# KAI.net
KiCad netlist of a schematic drawn in Altium Designer
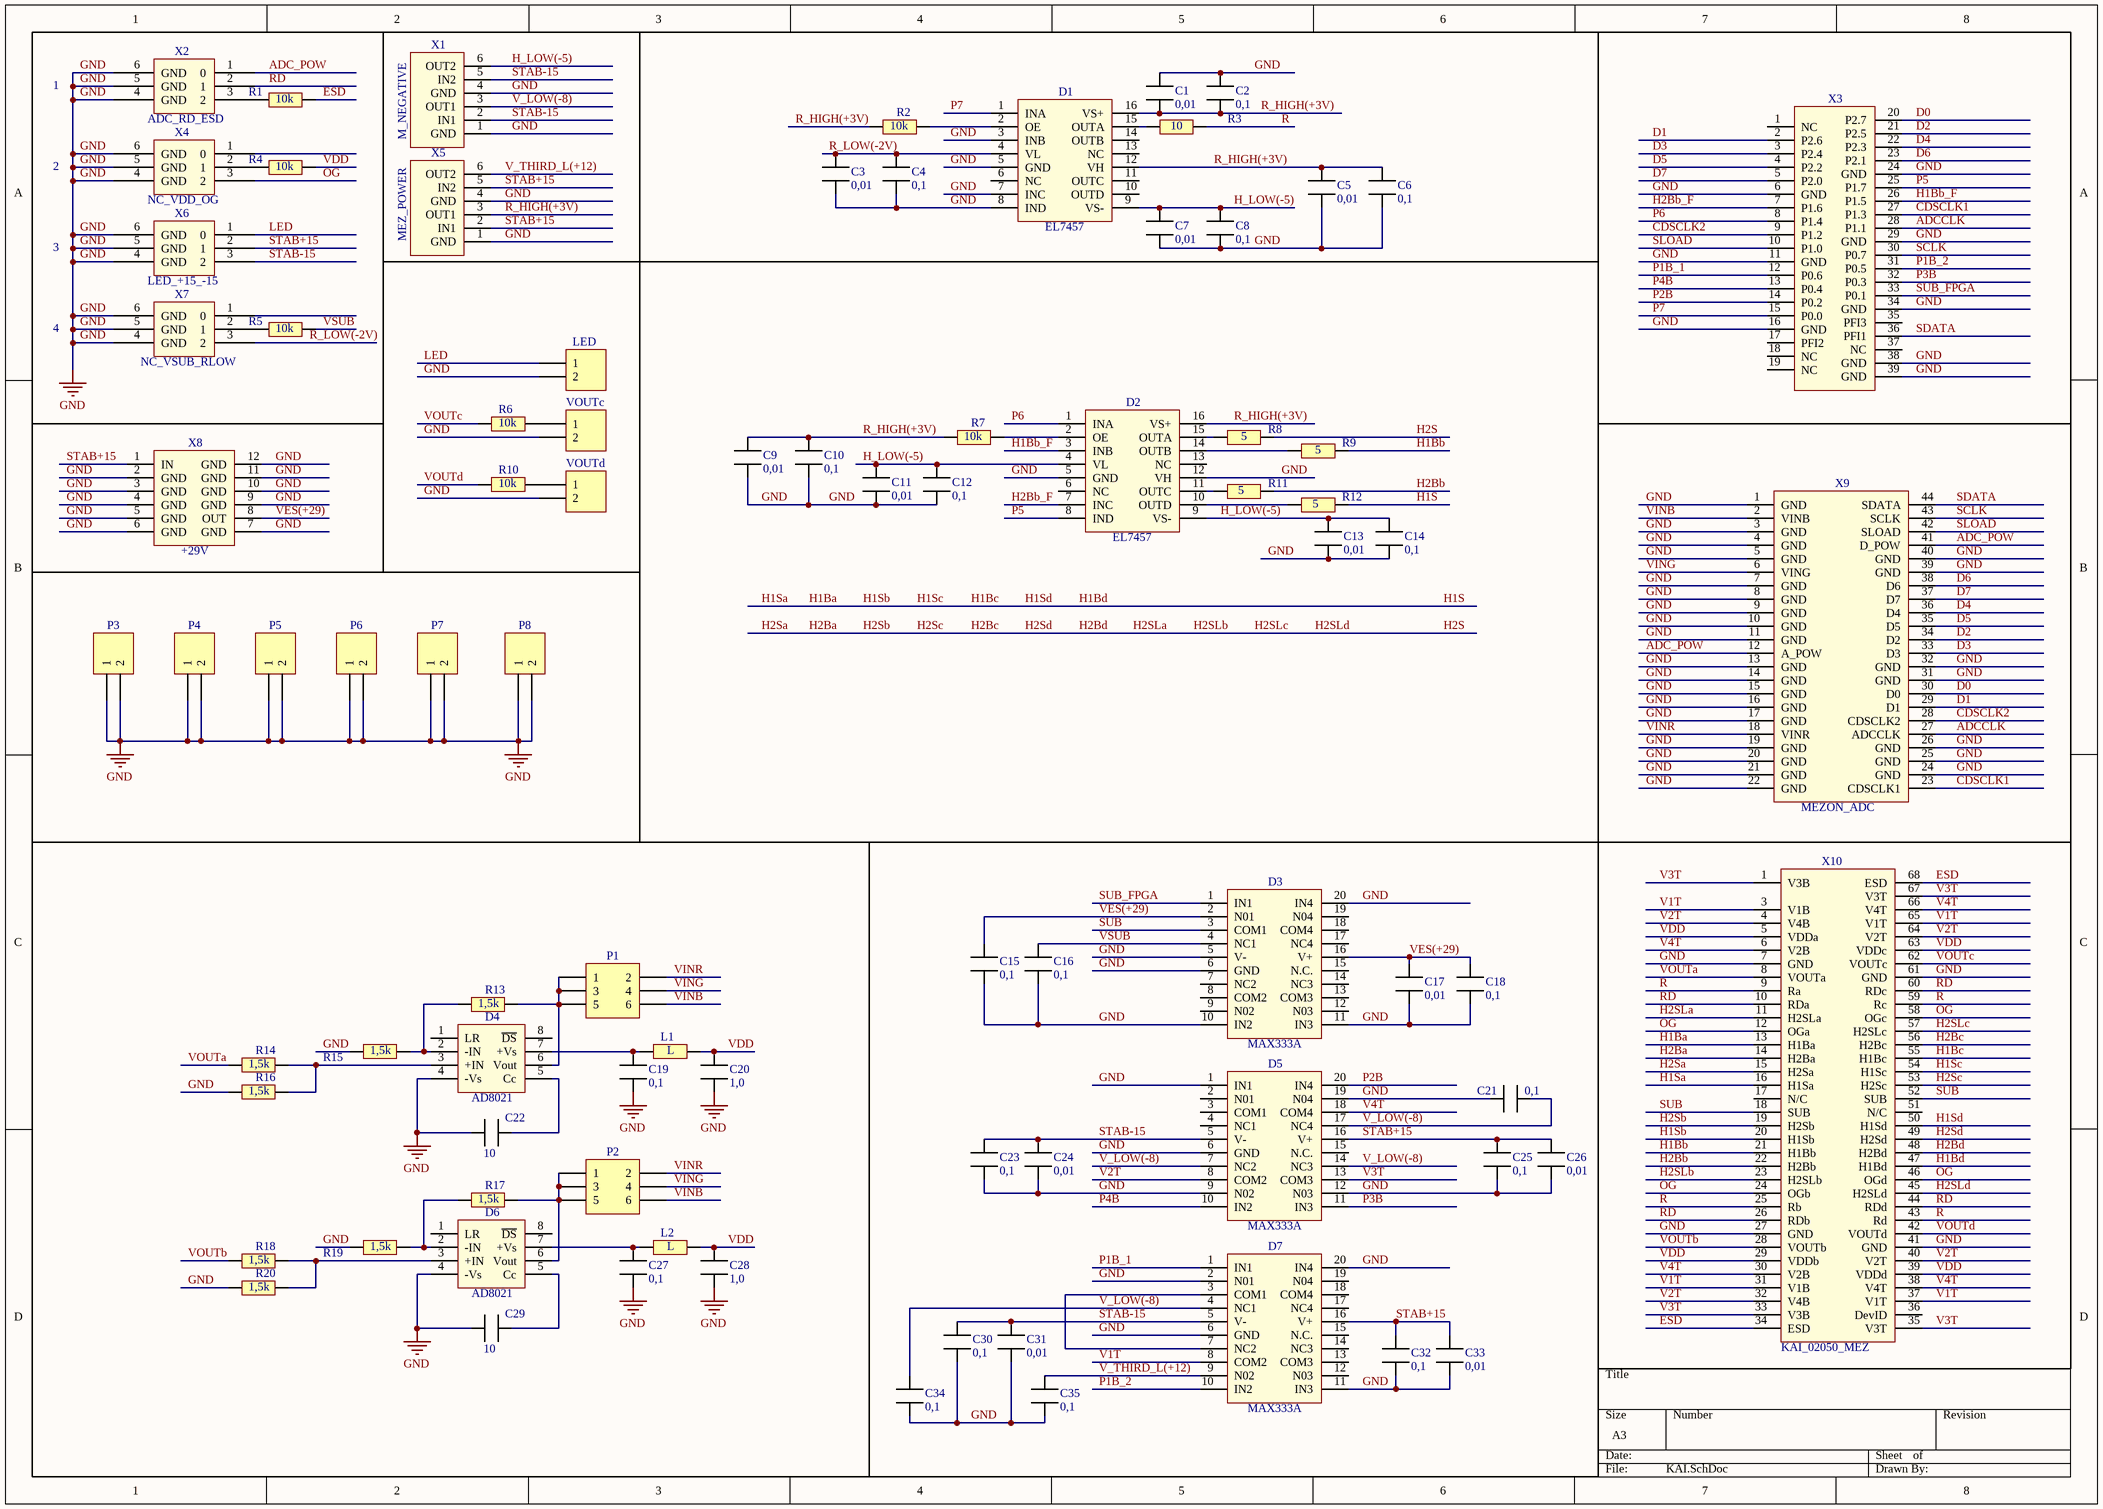
[diagram p0: KAI.SchDoc]

(export (version "E")
  (design (tool "Eeschema 10.0.6"))
  (components
    (comp (ref "C1") (value "0,01") (footprint "CAP_SMALL") (libsource (lib "Schlib") (part "CAP_SMALL")))
    (comp (ref "C2") (value "0,1") (footprint "CAP_SMALL") (libsource (lib "Schlib") (part "CAP_SMALL")))
    (comp (ref "C3") (value "0,01") (footprint "CAP_SMALL") (libsource (lib "Schlib") (part "CAP_SMALL")))
    (comp (ref "C4") (value "0,1") (footprint "CAP_SMALL") (libsource (lib "Schlib") (part "CAP_SMALL")))
    (comp (ref "C5") (value "0,01") (footprint "CAP_SMALL") (libsource (lib "Schlib") (part "CAP_SMALL")))
    (comp (ref "C6") (value "0,1") (footprint "CAP_SMALL") (libsource (lib "Schlib") (part "CAP_SMALL")))
    (comp (ref "C7") (value "0,01") (footprint "CAP_SMALL") (libsource (lib "Schlib") (part "CAP_SMALL")))
    (comp (ref "C8") (value "0,1") (footprint "CAP_SMALL") (libsource (lib "Schlib") (part "CAP_SMALL")))
    (comp (ref "C9") (value "0,01") (footprint "CAP_SMALL") (libsource (lib "Schlib") (part "CAP_SMALL")))
    (comp (ref "C10") (value "0,1") (footprint "CAP_SMALL") (libsource (lib "Schlib") (part "CAP_SMALL")))
    (comp (ref "C11") (value "0,01") (footprint "CAP_SMALL") (libsource (lib "Schlib") (part "CAP_SMALL")))
    (comp (ref "C12") (value "0,1") (footprint "CAP_SMALL") (libsource (lib "Schlib") (part "CAP_SMALL")))
    (comp (ref "C13") (value "0,01") (footprint "CAP_SMALL") (libsource (lib "Schlib") (part "CAP_SMALL")))
    (comp (ref "C14") (value "0,1") (footprint "CAP_SMALL") (libsource (lib "Schlib") (part "CAP_SMALL")))
    (comp (ref "C15") (value "0,1") (footprint "CAP_SMALL") (libsource (lib "Schlib") (part "CAP_SMALL")))
    (comp (ref "C16") (value "0,1") (footprint "CAP_SMALL") (libsource (lib "Schlib") (part "CAP_SMALL")))
    (comp (ref "C17") (value "0,01") (footprint "CAP_SMALL") (libsource (lib "Schlib") (part "CAP_SMALL")))
    (comp (ref "C18") (value "0,1") (footprint "CAP_SMALL") (libsource (lib "Schlib") (part "CAP_SMALL")))
    (comp (ref "C19") (value "0,1") (footprint "CAP_SMALL") (libsource (lib "Schlib") (part "CAP_SMALL")))
    (comp (ref "C20") (value "1,0") (footprint "CAP_SMALL") (libsource (lib "Schlib") (part "CAP_SMALL")))
    (comp (ref "C21") (value "0,1") (footprint "CAP_SMALL") (libsource (lib "Schlib") (part "CAP_SMALL")))
    (comp (ref "C22") (value "10") (footprint "CAP_SMALL") (libsource (lib "Schlib") (part "CAP_SMALL")))
    (comp (ref "C23") (value "0,1") (footprint "CAP_SMALL") (libsource (lib "Schlib") (part "CAP_SMALL")))
    (comp (ref "C24") (value "0,01") (footprint "CAP_SMALL") (libsource (lib "Schlib") (part "CAP_SMALL")))
    (comp (ref "C25") (value "0,1") (footprint "CAP_SMALL") (libsource (lib "Schlib") (part "CAP_SMALL")))
    (comp (ref "C26") (value "0,01") (footprint "CAP_SMALL") (libsource (lib "Schlib") (part "CAP_SMALL")))
    (comp (ref "C27") (value "0,1") (footprint "CAP_SMALL") (libsource (lib "Schlib") (part "CAP_SMALL")))
    (comp (ref "C28") (value "1,0") (footprint "CAP_SMALL") (libsource (lib "Schlib") (part "CAP_SMALL")))
    (comp (ref "C29") (value "10") (footprint "CAP_SMALL") (libsource (lib "Schlib") (part "CAP_SMALL")))
    (comp (ref "C30") (value "0,1") (footprint "CAP_SMALL") (libsource (lib "Schlib") (part "CAP_SMALL")))
    (comp (ref "C31") (value "0,01") (footprint "CAP_SMALL") (libsource (lib "Schlib") (part "CAP_SMALL")))
    (comp (ref "C32") (value "0,1") (footprint "CAP_SMALL") (libsource (lib "Schlib") (part "CAP_SMALL")))
    (comp (ref "C33") (value "0,01") (footprint "CAP_SMALL") (libsource (lib "Schlib") (part "CAP_SMALL")))
    (comp (ref "C34") (value "0,1") (footprint "CAP_SMALL") (libsource (lib "Schlib") (part "CAP_SMALL")))
    (comp (ref "C35") (value "0,1") (footprint "CAP_SMALL") (libsource (lib "Schlib") (part "CAP_SMALL")))
    (comp (ref "D1") (value "EL7457") (footprint "EL7457") (libsource (lib "Schlib") (part "EL7457")))
    (comp (ref "D2") (value "EL7457") (footprint "EL7457") (libsource (lib "Schlib") (part "EL7457")))
    (comp (ref "D3") (value "MAX333A") (footprint "MAX333A") (libsource (lib "Schlib") (part "MAX333A")))
    (comp (ref "D4") (value "AD8021") (footprint "AD8021") (libsource (lib "Schlib") (part "AD8021")))
    (comp (ref "D5") (value "MAX333A") (footprint "MAX333A") (libsource (lib "Schlib") (part "MAX333A")))
    (comp (ref "D6") (value "AD8021") (footprint "AD8021") (libsource (lib "Schlib") (part "AD8021")))
    (comp (ref "D7") (value "MAX333A") (footprint "MAX333A") (libsource (lib "Schlib") (part "MAX333A")))
    (comp (ref "L1") (value "L") (footprint "RES") (libsource (lib "Schlib") (part "RES")))
    (comp (ref "L2") (value "L") (footprint "RES") (libsource (lib "Schlib") (part "RES")))
    (comp (ref "LED")
      (value "Header 2")
      (footprint "HDR1X2")
      (description "Header, 2-Pin")
      (fields (field (name "PUBLISHER") "Altium Limited"))
      (libsource (lib "") (part "Header 2_1"))
    )
    (comp (ref "P1")
      (value "Header 3X2")
      (footprint "HDR2X3")
      (description "Header, 3-Pin, Dual row")
      (fields (field (name "PUBLISHER") "Altium Limited"))
      (libsource (lib "Miscellaneous Connectors") (part "Header 3X2"))
    )
    (comp (ref "P2")
      (value "Header 3X2")
      (footprint "HDR2X3")
      (description "Header, 3-Pin, Dual row")
      (fields (field (name "PUBLISHER") "Altium Limited"))
      (libsource (lib "Miscellaneous Connectors") (part "Header 3X2"))
    )
    (comp (ref "P3")
      (value "~")
      (footprint "HDR1X2")
      (description "Header, 2-Pin")
      (fields (field (name "PUBLISHER") "Altium Limited"))
      (libsource (lib "Miscellaneous Connectors") (part "Header 2"))
    )
    (comp (ref "P4")
      (value "~")
      (footprint "HDR1X2")
      (description "Header, 2-Pin")
      (fields (field (name "PUBLISHER") "Altium Limited"))
      (libsource (lib "Miscellaneous Connectors") (part "Header 2"))
    )
    (comp (ref "P5")
      (value "~")
      (footprint "HDR1X2")
      (description "Header, 2-Pin")
      (fields (field (name "PUBLISHER") "Altium Limited"))
      (libsource (lib "Miscellaneous Connectors") (part "Header 2"))
    )
    (comp (ref "P6")
      (value "~")
      (footprint "HDR1X2")
      (description "Header, 2-Pin")
      (fields (field (name "PUBLISHER") "Altium Limited"))
      (libsource (lib "Miscellaneous Connectors") (part "Header 2"))
    )
    (comp (ref "P7")
      (value "~")
      (footprint "HDR1X2")
      (description "Header, 2-Pin")
      (fields (field (name "PUBLISHER") "Altium Limited"))
      (libsource (lib "Miscellaneous Connectors") (part "Header 2"))
    )
    (comp (ref "P8")
      (value "~")
      (footprint "HDR1X2")
      (description "Header, 2-Pin")
      (fields (field (name "PUBLISHER") "Altium Limited"))
      (libsource (lib "Miscellaneous Connectors") (part "Header 2"))
    )
    (comp (ref "R1") (value "10k") (footprint "RES") (libsource (lib "Schlib") (part "RES")))
    (comp (ref "R2") (value "10k") (footprint "RES") (libsource (lib "Schlib") (part "RES")))
    (comp (ref "R3") (value "10") (footprint "RES") (libsource (lib "Schlib") (part "RES")))
    (comp (ref "R4") (value "10k") (footprint "RES") (libsource (lib "Schlib") (part "RES")))
    (comp (ref "R5") (value "10k") (footprint "RES") (libsource (lib "Schlib") (part "RES")))
    (comp (ref "R6") (value "10k") (footprint "RES") (libsource (lib "Schlib") (part "RES")))
    (comp (ref "R7") (value "10k") (footprint "RES") (libsource (lib "Schlib") (part "RES")))
    (comp (ref "R8") (value "5") (footprint "RES") (libsource (lib "Schlib") (part "RES")))
    (comp (ref "R9") (value "5") (footprint "RES") (libsource (lib "Schlib") (part "RES")))
    (comp (ref "R10") (value "10k") (footprint "RES") (libsource (lib "Schlib") (part "RES")))
    (comp (ref "R11") (value "5") (footprint "RES") (libsource (lib "Schlib") (part "RES")))
    (comp (ref "R12") (value "5") (footprint "RES") (libsource (lib "Schlib") (part "RES")))
    (comp (ref "R13") (value "1,5k") (footprint "RES") (libsource (lib "") (part "RES_1")))
    (comp (ref "R14") (value "1,5k") (footprint "RES") (libsource (lib "Schlib") (part "RES")))
    (comp (ref "R15") (value "1,5k") (footprint "RES") (libsource (lib "") (part "RES_1")))
    (comp (ref "R16") (value "1,5k") (footprint "RES") (libsource (lib "Schlib") (part "RES")))
    (comp (ref "R17") (value "1,5k") (footprint "RES") (libsource (lib "") (part "RES_1")))
    (comp (ref "R18") (value "1,5k") (footprint "RES") (libsource (lib "Schlib") (part "RES")))
    (comp (ref "R19") (value "1,5k") (footprint "RES") (libsource (lib "") (part "RES_1")))
    (comp (ref "R20") (value "1,5k") (footprint "RES") (libsource (lib "Schlib") (part "RES")))
    (comp (ref "VOUTc")
      (value "Header 2")
      (footprint "HDR1X2")
      (description "Header, 2-Pin")
      (fields (field (name "PUBLISHER") "Altium Limited"))
      (libsource (lib "") (part "Header 2_1"))
    )
    (comp (ref "VOUTd")
      (value "Header 2")
      (footprint "HDR1X2")
      (description "Header, 2-Pin")
      (fields (field (name "PUBLISHER") "Altium Limited"))
      (libsource (lib "") (part "Header 2_1"))
    )
    (comp (ref "X1")
      (value "M_NEGATIVE")
      (footprint "MEZON_POWER_NEGATIVE")
      (libsource (lib "Schlib") (part "MEZON_POWER_NEGATIVE"))
    )
    (comp (ref "X2") (value "ADC_RD_ESD") (footprint "POWER") (libsource (lib "Schlib") (part "POWER")))
    (comp (ref "X3")
      (value "CHEAP_CON_37_FEMALE")
      (footprint "CHEAP_CONN_FEMALE")
      (libsource (lib "Schlib") (part "CHEAP_CON_37_FEMALE"))
    )
    (comp (ref "X4") (value "NC_VDD_OG") (footprint "POWER") (libsource (lib "Schlib") (part "POWER")))
    (comp (ref "X5")
      (value "MEZ_POWER")
      (footprint "MEZON_POWER_NEW")
      (libsource (lib "Schlib") (part "MEZON_POWER_NEW"))
    )
    (comp (ref "X6") (value "LED_+15_-15") (footprint "POWER") (libsource (lib "Schlib") (part "POWER")))
    (comp (ref "X7") (value "NC_VSUB_RLOW") (footprint "POWER") (libsource (lib "Schlib") (part "POWER")))
    (comp (ref "X8")
      (value "+29V")
      (footprint "MEZON_STEP-UP")
      (libsource (lib "Schlib") (part "MEZON_STEP-UP"))
    )
    (comp (ref "X9")
      (value "MEZON_ADC")
      (footprint "MEZON_ADC")
      (libsource (lib "Schlib") (part "MEZON_ADC"))
    )
    (comp (ref "X10")
      (value "KAI_02050_MEZ")
      (footprint "KAI_02050_MEZONIN")
      (libsource (lib "Schlib") (part "KAI_02050_MEZON"))
    )
  )
  (nets
    (net (code "1") (name "/ADCCLK") (class "Default")
      (node (ref "X3") (pin "28") (pinfunction "P1.1_28") (pintype "passive"))
      (node (ref "X9") (pin "27") (pinfunction "ADCCLK_27") (pintype "passive"))
    )
    (net (code "2") (name "/ADC_POW") (class "Default")
      (node (ref "X2") (pin "1") (pinfunction "0_1") (pintype "passive"))
      (node (ref "X9") (pin "12") (pinfunction "A_POW_12") (pintype "passive"))
      (node (ref "X9") (pin "41") (pinfunction "D_POW_41") (pintype "passive"))
    )
    (net (code "3") (name "/CDSCLK1") (class "Default")
      (node (ref "X3") (pin "27") (pinfunction "P1.3_27") (pintype "passive"))
      (node (ref "X9") (pin "23") (pinfunction "CDSCLK1_23") (pintype "passive"))
    )
    (net (code "4") (name "/CDSCLK2") (class "Default")
      (node (ref "X3") (pin "9") (pinfunction "P1.2_9") (pintype "passive"))
      (node (ref "X9") (pin "28") (pinfunction "CDSCLK2_28") (pintype "passive"))
    )
    (net (code "5") (name "/D0") (class "Default")
      (node (ref "X3") (pin "20") (pinfunction "P2.7_20") (pintype "passive"))
      (node (ref "X9") (pin "30") (pinfunction "D0_30") (pintype "passive"))
    )
    (net (code "6") (name "/D1") (class "Default")
      (node (ref "X3") (pin "2") (pinfunction "P2.6_2") (pintype "passive"))
      (node (ref "X9") (pin "29") (pinfunction "D1_29") (pintype "passive"))
    )
    (net (code "7") (name "/D2") (class "Default")
      (node (ref "X3") (pin "21") (pinfunction "P2.5_21") (pintype "passive"))
      (node (ref "X9") (pin "34") (pinfunction "D2_34") (pintype "passive"))
    )
    (net (code "8") (name "/D3") (class "Default")
      (node (ref "X3") (pin "3") (pinfunction "P2.4_3") (pintype "passive"))
      (node (ref "X9") (pin "33") (pinfunction "D3_33") (pintype "passive"))
    )
    (net (code "9") (name "/D4") (class "Default")
      (node (ref "X3") (pin "22") (pinfunction "P2.3_22") (pintype "passive"))
      (node (ref "X9") (pin "36") (pinfunction "D4_36") (pintype "passive"))
    )
    (net (code "10") (name "/D5") (class "Default")
      (node (ref "X3") (pin "4") (pinfunction "P2.2_4") (pintype "passive"))
      (node (ref "X9") (pin "35") (pinfunction "D5_35") (pintype "passive"))
    )
    (net (code "11") (name "/D6") (class "Default")
      (node (ref "X3") (pin "23") (pinfunction "P2.1_23") (pintype "passive"))
      (node (ref "X9") (pin "38") (pinfunction "D6_38") (pintype "passive"))
    )
    (net (code "12") (name "/D7") (class "Default")
      (node (ref "X3") (pin "5") (pinfunction "P2.0_5") (pintype "passive"))
      (node (ref "X9") (pin "37") (pinfunction "D7_37") (pintype "passive"))
    )
    (net (code "13") (name "/ESD") (class "Default")
      (node (ref "R1") (pin "2") (pinfunction "2_2") (pintype "passive"))
      (node (ref "X10") (pin "34") (pinfunction "ESD_34") (pintype "passive"))
      (node (ref "X10") (pin "68") (pinfunction "ESD_68") (pintype "passive"))
    )
    (net (code "14") (name "/H1Ba") (class "Default")
      (node (ref "R12") (pin "2") (pinfunction "2_2") (pintype "passive"))
      (node (ref "X10") (pin "13") (pinfunction "H1Ba_13") (pintype "passive"))
      (node (ref "X10") (pin "16") (pinfunction "H1Sa_16") (pintype "passive"))
      (node (ref "X10") (pin "20") (pinfunction "H1Sb_20") (pintype "passive"))
      (node (ref "X10") (pin "47") (pinfunction "H1Bd_47") (pintype "passive"))
      (node (ref "X10") (pin "50") (pinfunction "H1Sd_50") (pintype "passive"))
      (node (ref "X10") (pin "54") (pinfunction "H1Sc_54") (pintype "passive"))
      (node (ref "X10") (pin "55") (pinfunction "H1Bc_55") (pintype "passive"))
    )
    (net (code "15") (name "/H1Bb") (class "Default")
      (node (ref "R9") (pin "2") (pinfunction "2_2") (pintype "passive"))
      (node (ref "X10") (pin "21") (pinfunction "H1Bb_21") (pintype "passive"))
    )
    (net (code "16") (name "/H1Bb_F") (class "Default")
      (node (ref "D2") (pin "3") (pinfunction "INB_3") (pintype "passive"))
      (node (ref "X3") (pin "26") (pinfunction "P1.5_26") (pintype "passive"))
    )
    (net (code "17") (name "/H2Ba") (class "Default")
      (node (ref "R8") (pin "2") (pinfunction "2_2") (pintype "passive"))
      (node (ref "X10") (pin "11") (pinfunction "H2SLa_11") (pintype "passive"))
      (node (ref "X10") (pin "14") (pinfunction "H2Ba_14") (pintype "passive"))
      (node (ref "X10") (pin "15") (pinfunction "H2Sa_15") (pintype "passive"))
      (node (ref "X10") (pin "19") (pinfunction "H2Sb_19") (pintype "passive"))
      (node (ref "X10") (pin "23") (pinfunction "H2SLb_23") (pintype "passive"))
      (node (ref "X10") (pin "45") (pinfunction "H2SLd_45") (pintype "passive"))
      (node (ref "X10") (pin "48") (pinfunction "H2Bd_48") (pintype "passive"))
      (node (ref "X10") (pin "49") (pinfunction "H2Sd_49") (pintype "passive"))
      (node (ref "X10") (pin "53") (pinfunction "H2Sc_53") (pintype "passive"))
      (node (ref "X10") (pin "56") (pinfunction "H2Bc_56") (pintype "passive"))
      (node (ref "X10") (pin "57") (pinfunction "H2SLc_57") (pintype "passive"))
    )
    (net (code "18") (name "/H2Bb") (class "Default")
      (node (ref "R11") (pin "2") (pinfunction "2_2") (pintype "passive"))
      (node (ref "X10") (pin "22") (pinfunction "H2Bb_22") (pintype "passive"))
    )
    (net (code "19") (name "/H2Bb_F") (class "Default")
      (node (ref "D2") (pin "7") (pinfunction "INC_7") (pintype "passive"))
      (node (ref "X3") (pin "7") (pinfunction "P1.6_7") (pintype "passive"))
    )
    (net (code "20") (name "/H_LOW(-5)") (class "Default")
      (node (ref "C11") (pin "1") (pinfunction "1_1") (pintype "passive"))
      (node (ref "C12") (pin "1") (pinfunction "1_1") (pintype "passive"))
      (node (ref "C13") (pin "1") (pinfunction "1_1") (pintype "passive"))
      (node (ref "C14") (pin "1") (pinfunction "1_1") (pintype "passive"))
      (node (ref "C7") (pin "1") (pinfunction "1_1") (pintype "passive"))
      (node (ref "C8") (pin "1") (pinfunction "1_1") (pintype "passive"))
      (node (ref "D1") (pin "9") (pinfunction "VS-_9") (pintype "passive"))
      (node (ref "D2") (pin "4") (pinfunction "VL_4") (pintype "passive"))
      (node (ref "D2") (pin "9") (pinfunction "VS-_9") (pintype "passive"))
      (node (ref "X1") (pin "6") (pinfunction "OUT2_6") (pintype "passive"))
    )
    (net (code "21") (name "/LED") (class "Default")
      (node (ref "LED") (pin "1") (pinfunction "1_1") (pintype "passive"))
      (node (ref "X6") (pin "1") (pinfunction "0_1") (pintype "passive"))
    )
    (net (code "22") (name "/OG") (class "Default")
      (node (ref "X10") (pin "12") (pinfunction "OGa_12") (pintype "passive"))
      (node (ref "X10") (pin "24") (pinfunction "OGb_24") (pintype "passive"))
      (node (ref "X10") (pin "46") (pinfunction "OGd_46") (pintype "passive"))
      (node (ref "X10") (pin "58") (pinfunction "OGc_58") (pintype "passive"))
      (node (ref "X4") (pin "3") (pinfunction "2_3") (pintype "passive"))
    )
    (net (code "23") (name "/P1B_1") (class "Default")
      (node (ref "D7") (pin "1") (pinfunction "IN1_1") (pintype "passive"))
      (node (ref "X3") (pin "12") (pinfunction "P0.6_12") (pintype "passive"))
    )
    (net (code "24") (name "/P1B_2") (class "Default")
      (node (ref "D7") (pin "10") (pinfunction "IN2_10") (pintype "passive"))
      (node (ref "X3") (pin "31") (pinfunction "P0.5_31") (pintype "passive"))
    )
    (net (code "25") (name "/P2B") (class "Default")
      (node (ref "D5") (pin "20") (pinfunction "IN4_20") (pintype "passive"))
      (node (ref "X3") (pin "14") (pinfunction "P0.2_14") (pintype "passive"))
    )
    (net (code "26") (name "/P3B") (class "Default")
      (node (ref "D5") (pin "11") (pinfunction "IN3_11") (pintype "passive"))
      (node (ref "X3") (pin "32") (pinfunction "P0.3_32") (pintype "passive"))
    )
    (net (code "27") (name "/P4B") (class "Default")
      (node (ref "D5") (pin "10") (pinfunction "IN2_10") (pintype "passive"))
      (node (ref "X3") (pin "13") (pinfunction "P0.4_13") (pintype "passive"))
    )
    (net (code "28") (name "/P5") (class "Default")
      (node (ref "D2") (pin "8") (pinfunction "IND_8") (pintype "passive"))
      (node (ref "X3") (pin "25") (pinfunction "P1.7_25") (pintype "passive"))
    )
    (net (code "29") (name "/P6") (class "Default")
      (node (ref "D2") (pin "1") (pinfunction "INA_1") (pintype "passive"))
      (node (ref "X3") (pin "8") (pinfunction "P1.4_8") (pintype "passive"))
    )
    (net (code "30") (name "/P7") (class "Default")
      (node (ref "D1") (pin "1") (pinfunction "INA_1") (pintype "passive"))
      (node (ref "X3") (pin "15") (pinfunction "P0.0_15") (pintype "passive"))
    )
    (net (code "31") (name "/R") (class "Default")
      (node (ref "R3") (pin "2") (pinfunction "2_2") (pintype "passive"))
      (node (ref "X10") (pin "25") (pinfunction "Rb_25") (pintype "passive"))
      (node (ref "X10") (pin "43") (pinfunction "Rd_43") (pintype "passive"))
      (node (ref "X10") (pin "59") (pinfunction "Rc_59") (pintype "passive"))
      (node (ref "X10") (pin "9") (pinfunction "Ra_9") (pintype "passive"))
    )
    (net (code "32") (name "/RD") (class "Default")
      (node (ref "X10") (pin "10") (pinfunction "RDa_10") (pintype "passive"))
      (node (ref "X10") (pin "26") (pinfunction "RDb_26") (pintype "passive"))
      (node (ref "X10") (pin "44") (pinfunction "RDd_44") (pintype "passive"))
      (node (ref "X10") (pin "60") (pinfunction "RDc_60") (pintype "passive"))
      (node (ref "X2") (pin "2") (pinfunction "1_2") (pintype "passive"))
    )
    (net (code "33") (name "/R_HIGH(+3V)") (class "Default")
      (node (ref "C1") (pin "2") (pinfunction "2_2") (pintype "passive"))
      (node (ref "C10") (pin "1") (pinfunction "1_1") (pintype "passive"))
      (node (ref "C2") (pin "2") (pinfunction "2_2") (pintype "passive"))
      (node (ref "C5") (pin "1") (pinfunction "1_1") (pintype "passive"))
      (node (ref "C6") (pin "1") (pinfunction "1_1") (pintype "passive"))
      (node (ref "C9") (pin "1") (pinfunction "1_1") (pintype "passive"))
      (node (ref "D1") (pin "12") (pinfunction "VH_12") (pintype "passive"))
      (node (ref "D1") (pin "16") (pinfunction "VS+_16") (pintype "passive"))
      (node (ref "D2") (pin "16") (pinfunction "VS+_16") (pintype "passive"))
      (node (ref "R2") (pin "1") (pinfunction "1_1") (pintype "passive"))
      (node (ref "R7") (pin "1") (pinfunction "1_1") (pintype "passive"))
      (node (ref "X5") (pin "3") (pinfunction "OUT1_3") (pintype "passive"))
    )
    (net (code "34") (name "/R_LOW(-2V)") (class "Default")
      (node (ref "C3") (pin "1") (pinfunction "1_1") (pintype "passive"))
      (node (ref "C4") (pin "1") (pinfunction "1_1") (pintype "passive"))
      (node (ref "D1") (pin "4") (pinfunction "VL_4") (pintype "passive"))
      (node (ref "X7") (pin "3") (pinfunction "2_3") (pintype "passive"))
    )
    (net (code "35") (name "/SCLK") (class "Default")
      (node (ref "X3") (pin "30") (pinfunction "P0.7_30") (pintype "passive"))
      (node (ref "X9") (pin "43") (pinfunction "SCLK_43") (pintype "passive"))
    )
    (net (code "36") (name "/SDATA") (class "Default")
      (node (ref "X3") (pin "36") (pinfunction "PFI1_36") (pintype "passive"))
      (node (ref "X9") (pin "44") (pinfunction "SDATA_44") (pintype "passive"))
    )
    (net (code "37") (name "/SLOAD") (class "Default")
      (node (ref "X3") (pin "10") (pinfunction "P1.0_10") (pintype "passive"))
      (node (ref "X9") (pin "42") (pinfunction "SLOAD_42") (pintype "passive"))
    )
    (net (code "38") (name "/STAB+15") (class "Default")
      (node (ref "C25") (pin "2") (pinfunction "2_2") (pintype "passive"))
      (node (ref "C26") (pin "2") (pinfunction "2_2") (pintype "passive"))
      (node (ref "C32") (pin "2") (pinfunction "2_2") (pintype "passive"))
      (node (ref "C33") (pin "2") (pinfunction "2_2") (pintype "passive"))
      (node (ref "D5") (pin "16") (pinfunction "V+_16") (pintype "passive"))
      (node (ref "D7") (pin "16") (pinfunction "V+_16") (pintype "passive"))
      (node (ref "X5") (pin "2") (pinfunction "IN1_2") (pintype "passive"))
      (node (ref "X5") (pin "5") (pinfunction "IN2_5") (pintype "passive"))
      (node (ref "X6") (pin "2") (pinfunction "1_2") (pintype "passive"))
      (node (ref "X8") (pin "1") (pinfunction "IN_1") (pintype "passive"))
    )
    (net (code "39") (name "/STAB-15") (class "Default")
      (node (ref "C23") (pin "2") (pinfunction "2_2") (pintype "passive"))
      (node (ref "C24") (pin "2") (pinfunction "2_2") (pintype "passive"))
      (node (ref "C30") (pin "2") (pinfunction "2_2") (pintype "passive"))
      (node (ref "C31") (pin "2") (pinfunction "2_2") (pintype "passive"))
      (node (ref "D5") (pin "5") (pinfunction "V-_5") (pintype "passive"))
      (node (ref "D7") (pin "5") (pinfunction "V-_5") (pintype "passive"))
      (node (ref "X1") (pin "2") (pinfunction "IN1_2") (pintype "passive"))
      (node (ref "X1") (pin "5") (pinfunction "IN2_5") (pintype "passive"))
      (node (ref "X6") (pin "3") (pinfunction "2_3") (pintype "passive"))
    )
    (net (code "40") (name "/SUB") (class "Default")
      (node (ref "D3") (pin "3") (pinfunction "COM1_3") (pintype "passive"))
      (node (ref "X10") (pin "18") (pinfunction "SUB_18") (pintype "passive"))
      (node (ref "X10") (pin "52") (pinfunction "SUB_52") (pintype "passive"))
    )
    (net (code "41") (name "/SUB_FPGA") (class "Default")
      (node (ref "D3") (pin "1") (pinfunction "IN1_1") (pintype "passive"))
      (node (ref "X3") (pin "33") (pinfunction "P0.1_33") (pintype "passive"))
    )
    (net (code "42") (name "/V1T") (class "Default")
      (node (ref "D7") (pin "8") (pinfunction "COM2_8") (pintype "passive"))
      (node (ref "X10") (pin "3") (pinfunction "V1B_3") (pintype "passive"))
      (node (ref "X10") (pin "31") (pinfunction "V1B_31") (pintype "passive"))
      (node (ref "X10") (pin "37") (pinfunction "V1T_37") (pintype "passive"))
      (node (ref "X10") (pin "65") (pinfunction "V1T_65") (pintype "passive"))
    )
    (net (code "43") (name "/V2T") (class "Default")
      (node (ref "D5") (pin "8") (pinfunction "COM2_8") (pintype "passive"))
      (node (ref "X10") (pin "32") (pinfunction "V4B_32") (pintype "passive"))
      (node (ref "X10") (pin "4") (pinfunction "V4B_4") (pintype "passive"))
      (node (ref "X10") (pin "40") (pinfunction "V2T_40") (pintype "passive"))
      (node (ref "X10") (pin "64") (pinfunction "V2T_64") (pintype "passive"))
    )
    (net (code "44") (name "/V3T") (class "Default")
      (node (ref "D5") (pin "13") (pinfunction "COM3_13") (pintype "passive"))
      (node (ref "X10") (pin "1") (pinfunction "V3B_1") (pintype "passive"))
      (node (ref "X10") (pin "33") (pinfunction "V3B_33") (pintype "passive"))
      (node (ref "X10") (pin "35") (pinfunction "V3T_35") (pintype "passive"))
      (node (ref "X10") (pin "67") (pinfunction "V3T_67") (pintype "passive"))
    )
    (net (code "45") (name "/V4T") (class "Default")
      (node (ref "D5") (pin "18") (pinfunction "COM4_18") (pintype "passive"))
      (node (ref "X10") (pin "30") (pinfunction "V2B_30") (pintype "passive"))
      (node (ref "X10") (pin "38") (pinfunction "V4T_38") (pintype "passive"))
      (node (ref "X10") (pin "6") (pinfunction "V2B_6") (pintype "passive"))
      (node (ref "X10") (pin "66") (pinfunction "V4T_66") (pintype "passive"))
    )
    (net (code "46") (name "/VDD") (class "Default")
      (node (ref "C20") (pin "2") (pinfunction "2_2") (pintype "passive"))
      (node (ref "C28") (pin "2") (pinfunction "2_2") (pintype "passive"))
      (node (ref "L1") (pin "2") (pinfunction "2_2") (pintype "passive"))
      (node (ref "L2") (pin "2") (pinfunction "2_2") (pintype "passive"))
      (node (ref "R4") (pin "2") (pinfunction "2_2") (pintype "passive"))
      (node (ref "X10") (pin "29") (pinfunction "VDDb_29") (pintype "passive"))
      (node (ref "X10") (pin "39") (pinfunction "VDDd_39") (pintype "passive"))
      (node (ref "X10") (pin "5") (pinfunction "VDDa_5") (pintype "passive"))
      (node (ref "X10") (pin "63") (pinfunction "VDDc_63") (pintype "passive"))
    )
    (net (code "47") (name "/VES(+29)") (class "Default")
      (node (ref "C15") (pin "1") (pinfunction "1_1") (pintype "passive"))
      (node (ref "C17") (pin "2") (pinfunction "2_2") (pintype "passive"))
      (node (ref "C18") (pin "2") (pinfunction "2_2") (pintype "passive"))
      (node (ref "D3") (pin "16") (pinfunction "V+_16") (pintype "passive"))
      (node (ref "D3") (pin "2") (pinfunction "N01_2") (pintype "passive"))
      (node (ref "X8") (pin "8") (pinfunction "OUT_8") (pintype "passive"))
    )
    (net (code "48") (name "/VINB") (class "Default")
      (node (ref "P1") (pin "6") (pinfunction "6_6") (pintype "passive"))
      (node (ref "P2") (pin "6") (pinfunction "6_6") (pintype "passive"))
      (node (ref "X9") (pin "2") (pinfunction "VINB_2") (pintype "passive"))
    )
    (net (code "49") (name "/VING") (class "Default")
      (node (ref "P1") (pin "4") (pinfunction "4_4") (pintype "passive"))
      (node (ref "P2") (pin "4") (pinfunction "4_4") (pintype "passive"))
      (node (ref "X9") (pin "6") (pinfunction "VING_6") (pintype "passive"))
    )
    (net (code "50") (name "/VINR") (class "Default")
      (node (ref "P1") (pin "2") (pinfunction "2_2") (pintype "passive"))
      (node (ref "P2") (pin "2") (pinfunction "2_2") (pintype "passive"))
      (node (ref "X9") (pin "18") (pinfunction "VINR_18") (pintype "passive"))
    )
    (net (code "51") (name "/VOUTa") (class "Default")
      (node (ref "R14") (pin "1") (pinfunction "1_1") (pintype "passive"))
      (node (ref "X10") (pin "8") (pinfunction "VOUTa_8") (pintype "passive"))
    )
    (net (code "52") (name "/VOUTb") (class "Default")
      (node (ref "R18") (pin "1") (pinfunction "1_1") (pintype "passive"))
      (node (ref "X10") (pin "28") (pinfunction "VOUTb_28") (pintype "passive"))
    )
    (net (code "53") (name "/VOUTc") (class "Default")
      (node (ref "R6") (pin "1") (pinfunction "1_1") (pintype "passive"))
      (node (ref "X10") (pin "62") (pinfunction "VOUTc_62") (pintype "passive"))
    )
    (net (code "54") (name "/VOUTd") (class "Default")
      (node (ref "R10") (pin "1") (pinfunction "1_1") (pintype "passive"))
      (node (ref "X10") (pin "42") (pinfunction "VOUTd_42") (pintype "passive"))
    )
    (net (code "55") (name "/VSUB") (class "Default")
      (node (ref "C16") (pin "1") (pinfunction "1_1") (pintype "passive"))
      (node (ref "D3") (pin "4") (pinfunction "NC1_4") (pintype "passive"))
      (node (ref "R5") (pin "2") (pinfunction "2_2") (pintype "passive"))
    )
    (net (code "56") (name "/V_LOW(-8)") (class "Default")
      (node (ref "C21") (pin "1") (pinfunction "1_1") (pintype "passive"))
      (node (ref "C34") (pin "2") (pinfunction "2_2") (pintype "passive"))
      (node (ref "D5") (pin "14") (pinfunction "NC3_14") (pintype "passive"))
      (node (ref "D5") (pin "17") (pinfunction "NC4_17") (pintype "passive"))
      (node (ref "D5") (pin "7") (pinfunction "NC2_7") (pintype "passive"))
      (node (ref "D7") (pin "4") (pinfunction "NC1_4") (pintype "passive"))
      (node (ref "X1") (pin "3") (pinfunction "OUT1_3") (pintype "passive"))
    )
    (net (code "57") (name "/V_THIRD_L(+12)") (class "Default")
      (node (ref "C35") (pin "2") (pinfunction "2_2") (pintype "passive"))
      (node (ref "D7") (pin "9") (pinfunction "N02_9") (pintype "passive"))
      (node (ref "X5") (pin "6") (pinfunction "OUT2_6") (pintype "passive"))
    )
    (net (code "58") (name "GND") (class "Default")
      (node (ref "C1") (pin "1") (pinfunction "1_1") (pintype "passive"))
      (node (ref "C10") (pin "2") (pinfunction "2_2") (pintype "passive"))
      (node (ref "C11") (pin "2") (pinfunction "2_2") (pintype "passive"))
      (node (ref "C12") (pin "2") (pinfunction "2_2") (pintype "passive"))
      (node (ref "C13") (pin "2") (pinfunction "2_2") (pintype "passive"))
      (node (ref "C14") (pin "2") (pinfunction "2_2") (pintype "passive"))
      (node (ref "C15") (pin "2") (pinfunction "2_2") (pintype "passive"))
      (node (ref "C16") (pin "2") (pinfunction "2_2") (pintype "passive"))
      (node (ref "C17") (pin "1") (pinfunction "1_1") (pintype "passive"))
      (node (ref "C18") (pin "1") (pinfunction "1_1") (pintype "passive"))
      (node (ref "C19") (pin "1") (pinfunction "1_1") (pintype "passive"))
      (node (ref "C2") (pin "1") (pinfunction "1_1") (pintype "passive"))
      (node (ref "C20") (pin "1") (pinfunction "1_1") (pintype "passive"))
      (node (ref "C21") (pin "2") (pinfunction "2_2") (pintype "passive"))
      (node (ref "C22") (pin "2") (pinfunction "2_2") (pintype "passive"))
      (node (ref "C23") (pin "1") (pinfunction "1_1") (pintype "passive"))
      (node (ref "C24") (pin "1") (pinfunction "1_1") (pintype "passive"))
      (node (ref "C25") (pin "1") (pinfunction "1_1") (pintype "passive"))
      (node (ref "C26") (pin "1") (pinfunction "1_1") (pintype "passive"))
      (node (ref "C27") (pin "1") (pinfunction "1_1") (pintype "passive"))
      (node (ref "C28") (pin "1") (pinfunction "1_1") (pintype "passive"))
      (node (ref "C29") (pin "2") (pinfunction "2_2") (pintype "passive"))
      (node (ref "C3") (pin "2") (pinfunction "2_2") (pintype "passive"))
      (node (ref "C30") (pin "1") (pinfunction "1_1") (pintype "passive"))
      (node (ref "C31") (pin "1") (pinfunction "1_1") (pintype "passive"))
      (node (ref "C32") (pin "1") (pinfunction "1_1") (pintype "passive"))
      (node (ref "C33") (pin "1") (pinfunction "1_1") (pintype "passive"))
      (node (ref "C34") (pin "1") (pinfunction "1_1") (pintype "passive"))
      (node (ref "C35") (pin "1") (pinfunction "1_1") (pintype "passive"))
      (node (ref "C4") (pin "2") (pinfunction "2_2") (pintype "passive"))
      (node (ref "C5") (pin "2") (pinfunction "2_2") (pintype "passive"))
      (node (ref "C6") (pin "2") (pinfunction "2_2") (pintype "passive"))
      (node (ref "C7") (pin "2") (pinfunction "2_2") (pintype "passive"))
      (node (ref "C8") (pin "2") (pinfunction "2_2") (pintype "passive"))
      (node (ref "C9") (pin "2") (pinfunction "2_2") (pintype "passive"))
      (node (ref "D1") (pin "3") (pinfunction "INB_3") (pintype "passive"))
      (node (ref "D1") (pin "5") (pinfunction "GND_5") (pintype "passive"))
      (node (ref "D1") (pin "7") (pinfunction "INC_7") (pintype "passive"))
      (node (ref "D1") (pin "8") (pinfunction "IND_8") (pintype "passive"))
      (node (ref "D2") (pin "12") (pinfunction "VH_12") (pintype "passive"))
      (node (ref "D2") (pin "5") (pinfunction "GND_5") (pintype "passive"))
      (node (ref "D3") (pin "10") (pinfunction "IN2_10") (pintype "passive"))
      (node (ref "D3") (pin "11") (pinfunction "IN3_11") (pintype "passive"))
      (node (ref "D3") (pin "20") (pinfunction "IN4_20") (pintype "passive"))
      (node (ref "D3") (pin "5") (pinfunction "V-_5") (pintype "passive"))
      (node (ref "D3") (pin "6") (pinfunction "GND_6") (pintype "passive"))
      (node (ref "D4") (pin "4") (pinfunction "-Vs_4") (pintype "passive"))
      (node (ref "D5") (pin "1") (pinfunction "IN1_1") (pintype "passive"))
      (node (ref "D5") (pin "12") (pinfunction "N03_12") (pintype "passive"))
      (node (ref "D5") (pin "19") (pinfunction "N04_19") (pintype "passive"))
      (node (ref "D5") (pin "6") (pinfunction "GND_6") (pintype "passive"))
      (node (ref "D5") (pin "9") (pinfunction "N02_9") (pintype "passive"))
      (node (ref "D6") (pin "4") (pinfunction "-Vs_4") (pintype "passive"))
      (node (ref "D7") (pin "11") (pinfunction "IN3_11") (pintype "passive"))
      (node (ref "D7") (pin "2") (pinfunction "N01_2") (pintype "passive"))
      (node (ref "D7") (pin "20") (pinfunction "IN4_20") (pintype "passive"))
      (node (ref "D7") (pin "6") (pinfunction "GND_6") (pintype "passive"))
      (node (ref "LED") (pin "2") (pinfunction "2_2") (pintype "passive"))
      (node (ref "P3") (pin "1") (pinfunction "1_1") (pintype "passive"))
      (node (ref "P3") (pin "2") (pinfunction "2_2") (pintype "passive"))
      (node (ref "P4") (pin "1") (pinfunction "1_1") (pintype "passive"))
      (node (ref "P4") (pin "2") (pinfunction "2_2") (pintype "passive"))
      (node (ref "P5") (pin "1") (pinfunction "1_1") (pintype "passive"))
      (node (ref "P5") (pin "2") (pinfunction "2_2") (pintype "passive"))
      (node (ref "P6") (pin "1") (pinfunction "1_1") (pintype "passive"))
      (node (ref "P6") (pin "2") (pinfunction "2_2") (pintype "passive"))
      (node (ref "P7") (pin "1") (pinfunction "1_1") (pintype "passive"))
      (node (ref "P7") (pin "2") (pinfunction "2_2") (pintype "passive"))
      (node (ref "P8") (pin "1") (pinfunction "1_1") (pintype "passive"))
      (node (ref "P8") (pin "2") (pinfunction "2_2") (pintype "passive"))
      (node (ref "R15") (pin "2") (pinfunction "2_2") (pintype "passive"))
      (node (ref "R16") (pin "1") (pinfunction "1_1") (pintype "passive"))
      (node (ref "R19") (pin "2") (pinfunction "2_2") (pintype "passive"))
      (node (ref "R20") (pin "1") (pinfunction "1_1") (pintype "passive"))
      (node (ref "VOUTc") (pin "2") (pinfunction "2_2") (pintype "passive"))
      (node (ref "VOUTd") (pin "2") (pinfunction "2_2") (pintype "passive"))
      (node (ref "X1") (pin "1") (pinfunction "GND_1") (pintype "passive"))
      (node (ref "X1") (pin "4") (pinfunction "GND_4") (pintype "passive"))
      (node (ref "X10") (pin "27") (pinfunction "GND_27") (pintype "passive"))
      (node (ref "X10") (pin "41") (pinfunction "GND_41") (pintype "passive"))
      (node (ref "X10") (pin "61") (pinfunction "GND_61") (pintype "passive"))
      (node (ref "X10") (pin "7") (pinfunction "GND_7") (pintype "passive"))
      (node (ref "X2") (pin "4") (pinfunction "GND_4") (pintype "passive"))
      (node (ref "X2") (pin "5") (pinfunction "GND_5") (pintype "passive"))
      (node (ref "X2") (pin "6") (pinfunction "GND_6") (pintype "passive"))
      (node (ref "X3") (pin "11") (pinfunction "GND_11") (pintype "passive"))
      (node (ref "X3") (pin "16") (pinfunction "GND_16") (pintype "passive"))
      (node (ref "X3") (pin "24") (pinfunction "GND_24") (pintype "passive"))
      (node (ref "X3") (pin "29") (pinfunction "GND_29") (pintype "passive"))
      (node (ref "X3") (pin "34") (pinfunction "GND_34") (pintype "passive"))
      (node (ref "X3") (pin "38") (pinfunction "GND_38") (pintype "passive"))
      (node (ref "X3") (pin "39") (pinfunction "GND_39") (pintype "passive"))
      (node (ref "X3") (pin "6") (pinfunction "GND_6") (pintype "passive"))
      (node (ref "X4") (pin "4") (pinfunction "GND_4") (pintype "passive"))
      (node (ref "X4") (pin "5") (pinfunction "GND_5") (pintype "passive"))
      (node (ref "X4") (pin "6") (pinfunction "GND_6") (pintype "passive"))
      (node (ref "X5") (pin "1") (pinfunction "GND_1") (pintype "passive"))
      (node (ref "X5") (pin "4") (pinfunction "GND_4") (pintype "passive"))
      (node (ref "X6") (pin "4") (pinfunction "GND_4") (pintype "passive"))
      (node (ref "X6") (pin "5") (pinfunction "GND_5") (pintype "passive"))
      (node (ref "X6") (pin "6") (pinfunction "GND_6") (pintype "passive"))
      (node (ref "X7") (pin "4") (pinfunction "GND_4") (pintype "passive"))
      (node (ref "X7") (pin "5") (pinfunction "GND_5") (pintype "passive"))
      (node (ref "X7") (pin "6") (pinfunction "GND_6") (pintype "passive"))
      (node (ref "X8") (pin "10") (pinfunction "GND_10") (pintype "passive"))
      (node (ref "X8") (pin "11") (pinfunction "GND_11") (pintype "passive"))
      (node (ref "X8") (pin "12") (pinfunction "GND_12") (pintype "passive"))
      (node (ref "X8") (pin "2") (pinfunction "GND_2") (pintype "passive"))
      (node (ref "X8") (pin "3") (pinfunction "GND_3") (pintype "passive"))
      (node (ref "X8") (pin "4") (pinfunction "GND_4") (pintype "passive"))
      (node (ref "X8") (pin "5") (pinfunction "GND_5") (pintype "passive"))
      (node (ref "X8") (pin "6") (pinfunction "GND_6") (pintype "passive"))
      (node (ref "X8") (pin "7") (pinfunction "GND_7") (pintype "passive"))
      (node (ref "X8") (pin "9") (pinfunction "GND_9") (pintype "passive"))
      (node (ref "X9") (pin "1") (pinfunction "GND_1") (pintype "passive"))
      (node (ref "X9") (pin "10") (pinfunction "GND_10") (pintype "passive"))
      (node (ref "X9") (pin "11") (pinfunction "GND_11") (pintype "passive"))
      (node (ref "X9") (pin "13") (pinfunction "GND_13") (pintype "passive"))
      (node (ref "X9") (pin "14") (pinfunction "GND_14") (pintype "passive"))
      (node (ref "X9") (pin "15") (pinfunction "GND_15") (pintype "passive"))
      (node (ref "X9") (pin "16") (pinfunction "GND_16") (pintype "passive"))
      (node (ref "X9") (pin "17") (pinfunction "GND_17") (pintype "passive"))
      (node (ref "X9") (pin "19") (pinfunction "GND_19") (pintype "passive"))
      (node (ref "X9") (pin "20") (pinfunction "GND_20") (pintype "passive"))
      (node (ref "X9") (pin "21") (pinfunction "GND_21") (pintype "passive"))
      (node (ref "X9") (pin "22") (pinfunction "GND_22") (pintype "passive"))
      (node (ref "X9") (pin "24") (pinfunction "GND_24") (pintype "passive"))
      (node (ref "X9") (pin "25") (pinfunction "GND_25") (pintype "passive"))
      (node (ref "X9") (pin "26") (pinfunction "GND_26") (pintype "passive"))
      (node (ref "X9") (pin "3") (pinfunction "GND_3") (pintype "passive"))
      (node (ref "X9") (pin "31") (pinfunction "GND_31") (pintype "passive"))
      (node (ref "X9") (pin "32") (pinfunction "GND_32") (pintype "passive"))
      (node (ref "X9") (pin "39") (pinfunction "GND_39") (pintype "passive"))
      (node (ref "X9") (pin "4") (pinfunction "GND_4") (pintype "passive"))
      (node (ref "X9") (pin "40") (pinfunction "GND_40") (pintype "passive"))
      (node (ref "X9") (pin "5") (pinfunction "GND_5") (pintype "passive"))
      (node (ref "X9") (pin "7") (pinfunction "GND_7") (pintype "passive"))
      (node (ref "X9") (pin "8") (pinfunction "GND_8") (pintype "passive"))
      (node (ref "X9") (pin "9") (pinfunction "GND_9") (pintype "passive"))
    )
    (net (code "59") (name "Net-(D1-OE)") (class "Default")
      (node (ref "D1") (pin "2") (pinfunction "OE_2") (pintype "passive"))
      (node (ref "R2") (pin "2") (pinfunction "2_2") (pintype "passive"))
    )
    (net (code "60") (name "Net-(D1-OUTA)") (class "Default")
      (node (ref "D1") (pin "15") (pinfunction "OUTA_15") (pintype "passive"))
      (node (ref "R3") (pin "1") (pinfunction "1_1") (pintype "passive"))
    )
    (net (code "61") (name "Net-(D2-OE)") (class "Default")
      (node (ref "D2") (pin "2") (pinfunction "OE_2") (pintype "passive"))
      (node (ref "R7") (pin "2") (pinfunction "2_2") (pintype "passive"))
    )
    (net (code "62") (name "Net-(D2-OUTA)") (class "Default")
      (node (ref "D2") (pin "15") (pinfunction "OUTA_15") (pintype "passive"))
      (node (ref "R8") (pin "1") (pinfunction "1_1") (pintype "passive"))
    )
    (net (code "63") (name "Net-(D2-OUTB)") (class "Default")
      (node (ref "D2") (pin "14") (pinfunction "OUTB_14") (pintype "passive"))
      (node (ref "R9") (pin "1") (pinfunction "1_1") (pintype "passive"))
    )
    (net (code "64") (name "Net-(D2-OUTC)") (class "Default")
      (node (ref "D2") (pin "11") (pinfunction "OUTC_11") (pintype "passive"))
      (node (ref "R11") (pin "1") (pinfunction "1_1") (pintype "passive"))
    )
    (net (code "65") (name "Net-(D2-OUTD)") (class "Default")
      (node (ref "D2") (pin "10") (pinfunction "OUTD_10") (pintype "passive"))
      (node (ref "R12") (pin "1") (pinfunction "1_1") (pintype "passive"))
    )
    (net (code "66") (name "Net-(D4-+IN)") (class "Default")
      (node (ref "D4") (pin "3") (pinfunction "+IN_3") (pintype "passive"))
      (node (ref "R14") (pin "2") (pinfunction "2_2") (pintype "passive"))
      (node (ref "R16") (pin "2") (pinfunction "2_2") (pintype "passive"))
    )
    (net (code "67") (name "Net-(D4-+Vs)") (class "Default")
      (node (ref "C19") (pin "2") (pinfunction "2_2") (pintype "passive"))
      (node (ref "D4") (pin "7") (pinfunction "+Vs_7") (pintype "passive"))
      (node (ref "L1") (pin "1") (pinfunction "1_1") (pintype "passive"))
    )
    (net (code "68") (name "Net-(D4--IN)") (class "Default")
      (node (ref "D4") (pin "2") (pinfunction "-IN_2") (pintype "passive"))
      (node (ref "R13") (pin "2") (pinfunction "2_2") (pintype "passive"))
      (node (ref "R15") (pin "1") (pinfunction "1_1") (pintype "passive"))
    )
    (net (code "69") (name "Net-(D4-Cc)") (class "Default")
      (node (ref "C22") (pin "1") (pinfunction "1_1") (pintype "passive"))
      (node (ref "D4") (pin "5") (pinfunction "Cc_5") (pintype "passive"))
    )
    (net (code "70") (name "Net-(D4-Vout)") (class "Default")
      (node (ref "D4") (pin "6") (pinfunction "Vout_6") (pintype "passive"))
      (node (ref "P1") (pin "1") (pinfunction "1_1") (pintype "passive"))
      (node (ref "P1") (pin "3") (pinfunction "3_3") (pintype "passive"))
      (node (ref "P1") (pin "5") (pinfunction "5_5") (pintype "passive"))
      (node (ref "R13") (pin "1") (pinfunction "1_1") (pintype "passive"))
    )
    (net (code "71") (name "Net-(D6-+IN)") (class "Default")
      (node (ref "D6") (pin "3") (pinfunction "+IN_3") (pintype "passive"))
      (node (ref "R18") (pin "2") (pinfunction "2_2") (pintype "passive"))
      (node (ref "R20") (pin "2") (pinfunction "2_2") (pintype "passive"))
    )
    (net (code "72") (name "Net-(D6-+Vs)") (class "Default")
      (node (ref "C27") (pin "2") (pinfunction "2_2") (pintype "passive"))
      (node (ref "D6") (pin "7") (pinfunction "+Vs_7") (pintype "passive"))
      (node (ref "L2") (pin "1") (pinfunction "1_1") (pintype "passive"))
    )
    (net (code "73") (name "Net-(D6--IN)") (class "Default")
      (node (ref "D6") (pin "2") (pinfunction "-IN_2") (pintype "passive"))
      (node (ref "R17") (pin "2") (pinfunction "2_2") (pintype "passive"))
      (node (ref "R19") (pin "1") (pinfunction "1_1") (pintype "passive"))
    )
    (net (code "74") (name "Net-(D6-Cc)") (class "Default")
      (node (ref "C29") (pin "1") (pinfunction "1_1") (pintype "passive"))
      (node (ref "D6") (pin "5") (pinfunction "Cc_5") (pintype "passive"))
    )
    (net (code "75") (name "Net-(D6-Vout)") (class "Default")
      (node (ref "D6") (pin "6") (pinfunction "Vout_6") (pintype "passive"))
      (node (ref "P2") (pin "1") (pinfunction "1_1") (pintype "passive"))
      (node (ref "P2") (pin "3") (pinfunction "3_3") (pintype "passive"))
      (node (ref "P2") (pin "5") (pinfunction "5_5") (pintype "passive"))
      (node (ref "R17") (pin "1") (pinfunction "1_1") (pintype "passive"))
    )
    (net (code "76") (name "Net-(D7-COM1)") (class "Default")
      (node (ref "D7") (pin "3") (pinfunction "COM1_3") (pintype "passive"))
      (node (ref "D7") (pin "7") (pinfunction "NC2_7") (pintype "passive"))
    )
    (net (code "77") (name "Net-(R6-Pad2)") (class "Default")
      (node (ref "R6") (pin "2") (pinfunction "2_2") (pintype "passive"))
      (node (ref "VOUTc") (pin "1") (pinfunction "1_1") (pintype "passive"))
    )
    (net (code "78") (name "Net-(R10-Pad2)") (class "Default")
      (node (ref "R10") (pin "2") (pinfunction "2_2") (pintype "passive"))
      (node (ref "VOUTd") (pin "1") (pinfunction "1_1") (pintype "passive"))
    )
    (net (code "79") (name "Net-(X2-2)") (class "Default")
      (node (ref "R1") (pin "1") (pinfunction "1_1") (pintype "passive"))
      (node (ref "X2") (pin "3") (pinfunction "2_3") (pintype "passive"))
    )
    (net (code "80") (name "Net-(X4-1)") (class "Default")
      (node (ref "R4") (pin "1") (pinfunction "1_1") (pintype "passive"))
      (node (ref "X4") (pin "2") (pinfunction "1_2") (pintype "passive"))
    )
    (net (code "81") (name "Net-(X7-1)") (class "Default")
      (node (ref "R5") (pin "1") (pinfunction "1_1") (pintype "passive"))
      (node (ref "X7") (pin "2") (pinfunction "1_2") (pintype "passive"))
    )
    (net (code "82") (name "unconnected-(D1-NC-Pad6)") (class "Default")
      (node (ref "D1") (pin "6") (pinfunction "NC_6") (pintype "passive"))
    )
    (net (code "83") (name "unconnected-(D1-NC-Pad13)") (class "Default")
      (node (ref "D1") (pin "13") (pinfunction "NC_13") (pintype "passive"))
    )
    (net (code "84") (name "unconnected-(D1-OUTB-Pad14)") (class "Default")
      (node (ref "D1") (pin "14") (pinfunction "OUTB_14") (pintype "passive"))
    )
    (net (code "85") (name "unconnected-(D1-OUTC-Pad11)") (class "Default")
      (node (ref "D1") (pin "11") (pinfunction "OUTC_11") (pintype "passive"))
    )
    (net (code "86") (name "unconnected-(D1-OUTD-Pad10)") (class "Default")
      (node (ref "D1") (pin "10") (pinfunction "OUTD_10") (pintype "passive"))
    )
    (net (code "87") (name "unconnected-(D2-NC-Pad6)") (class "Default")
      (node (ref "D2") (pin "6") (pinfunction "NC_6") (pintype "passive"))
    )
    (net (code "88") (name "unconnected-(D2-NC-Pad13)") (class "Default")
      (node (ref "D2") (pin "13") (pinfunction "NC_13") (pintype "passive"))
    )
    (net (code "89") (name "unconnected-(D3-COM2-Pad8)") (class "Default")
      (node (ref "D3") (pin "8") (pinfunction "COM2_8") (pintype "passive"))
    )
    (net (code "90") (name "unconnected-(D3-COM3-Pad13)") (class "Default")
      (node (ref "D3") (pin "13") (pinfunction "COM3_13") (pintype "passive"))
    )
    (net (code "91") (name "unconnected-(D3-COM4-Pad18)") (class "Default")
      (node (ref "D3") (pin "18") (pinfunction "COM4_18") (pintype "passive"))
    )
    (net (code "92") (name "unconnected-(D3-N.C.-Pad15)") (class "Default")
      (node (ref "D3") (pin "15") (pinfunction "N.C._15") (pintype "passive"))
    )
    (net (code "93") (name "unconnected-(D3-N02-Pad9)") (class "Default")
      (node (ref "D3") (pin "9") (pinfunction "N02_9") (pintype "passive"))
    )
    (net (code "94") (name "unconnected-(D3-N03-Pad12)") (class "Default")
      (node (ref "D3") (pin "12") (pinfunction "N03_12") (pintype "passive"))
    )
    (net (code "95") (name "unconnected-(D3-N04-Pad19)") (class "Default")
      (node (ref "D3") (pin "19") (pinfunction "N04_19") (pintype "passive"))
    )
    (net (code "96") (name "unconnected-(D3-NC2-Pad7)") (class "Default")
      (node (ref "D3") (pin "7") (pinfunction "NC2_7") (pintype "passive"))
    )
    (net (code "97") (name "unconnected-(D3-NC3-Pad14)") (class "Default")
      (node (ref "D3") (pin "14") (pinfunction "NC3_14") (pintype "passive"))
    )
    (net (code "98") (name "unconnected-(D3-NC4-Pad17)") (class "Default")
      (node (ref "D3") (pin "17") (pinfunction "NC4_17") (pintype "passive"))
    )
    (net (code "99") (name "unconnected-(D4-LR-Pad1)") (class "Default")
      (node (ref "D4") (pin "1") (pinfunction "LR_1") (pintype "passive"))
    )
    (net (code "100") (name "unconnected-(D4-~{DS}-Pad8)") (class "Default")
      (node (ref "D4") (pin "8") (pinfunction "~{DS}_8") (pintype "passive"))
    )
    (net (code "101") (name "unconnected-(D5-COM1-Pad3)") (class "Default")
      (node (ref "D5") (pin "3") (pinfunction "COM1_3") (pintype "passive"))
    )
    (net (code "102") (name "unconnected-(D5-N.C.-Pad15)") (class "Default")
      (node (ref "D5") (pin "15") (pinfunction "N.C._15") (pintype "passive"))
    )
    (net (code "103") (name "unconnected-(D5-N01-Pad2)") (class "Default")
      (node (ref "D5") (pin "2") (pinfunction "N01_2") (pintype "passive"))
    )
    (net (code "104") (name "unconnected-(D5-NC1-Pad4)") (class "Default")
      (node (ref "D5") (pin "4") (pinfunction "NC1_4") (pintype "passive"))
    )
    (net (code "105") (name "unconnected-(D6-LR-Pad1)") (class "Default")
      (node (ref "D6") (pin "1") (pinfunction "LR_1") (pintype "passive"))
    )
    (net (code "106") (name "unconnected-(D6-~{DS}-Pad8)") (class "Default")
      (node (ref "D6") (pin "8") (pinfunction "~{DS}_8") (pintype "passive"))
    )
    (net (code "107") (name "unconnected-(D7-COM3-Pad13)") (class "Default")
      (node (ref "D7") (pin "13") (pinfunction "COM3_13") (pintype "passive"))
    )
    (net (code "108") (name "unconnected-(D7-COM4-Pad18)") (class "Default")
      (node (ref "D7") (pin "18") (pinfunction "COM4_18") (pintype "passive"))
    )
    (net (code "109") (name "unconnected-(D7-N.C.-Pad15)") (class "Default")
      (node (ref "D7") (pin "15") (pinfunction "N.C._15") (pintype "passive"))
    )
    (net (code "110") (name "unconnected-(D7-N03-Pad12)") (class "Default")
      (node (ref "D7") (pin "12") (pinfunction "N03_12") (pintype "passive"))
    )
    (net (code "111") (name "unconnected-(D7-N04-Pad19)") (class "Default")
      (node (ref "D7") (pin "19") (pinfunction "N04_19") (pintype "passive"))
    )
    (net (code "112") (name "unconnected-(D7-NC3-Pad14)") (class "Default")
      (node (ref "D7") (pin "14") (pinfunction "NC3_14") (pintype "passive"))
    )
    (net (code "113") (name "unconnected-(D7-NC4-Pad17)") (class "Default")
      (node (ref "D7") (pin "17") (pinfunction "NC4_17") (pintype "passive"))
    )
    (net (code "114") (name "unconnected-(X3-NC-Pad1)") (class "Default")
      (node (ref "X3") (pin "1") (pinfunction "NC_1") (pintype "passive"))
    )
    (net (code "115") (name "unconnected-(X3-NC-Pad18)") (class "Default")
      (node (ref "X3") (pin "18") (pinfunction "NC_18") (pintype "passive"))
    )
    (net (code "116") (name "unconnected-(X3-NC-Pad19)") (class "Default")
      (node (ref "X3") (pin "19") (pinfunction "NC_19") (pintype "passive"))
    )
    (net (code "117") (name "unconnected-(X3-NC-Pad37)") (class "Default")
      (node (ref "X3") (pin "37") (pinfunction "NC_37") (pintype "passive"))
    )
    (net (code "118") (name "unconnected-(X3-PFI2-Pad17)") (class "Default")
      (node (ref "X3") (pin "17") (pinfunction "PFI2_17") (pintype "passive"))
    )
    (net (code "119") (name "unconnected-(X3-PFI3-Pad35)") (class "Default")
      (node (ref "X3") (pin "35") (pinfunction "PFI3_35") (pintype "passive"))
    )
    (net (code "120") (name "unconnected-(X4-0-Pad1)") (class "Default")
      (node (ref "X4") (pin "1") (pinfunction "0_1") (pintype "passive"))
    )
    (net (code "121") (name "unconnected-(X7-0-Pad1)") (class "Default")
      (node (ref "X7") (pin "1") (pinfunction "0_1") (pintype "passive"))
    )
    (net (code "122") (name "unconnected-(X10-DevID-Pad36)") (class "Default")
      (node (ref "X10") (pin "36") (pinfunction "DevID_36") (pintype "passive"))
    )
    (net (code "123") (name "unconnected-(X10-N{slash}C-Pad17)") (class "Default")
      (node (ref "X10") (pin "17") (pinfunction "N/C_17") (pintype "passive"))
    )
    (net (code "124") (name "unconnected-(X10-N{slash}C-Pad51)") (class "Default")
      (node (ref "X10") (pin "51") (pinfunction "N/C_51") (pintype "passive"))
    )
  )
)
